# command_radiateur.net
KiCad netlist of a schematic drawn in EAGLE
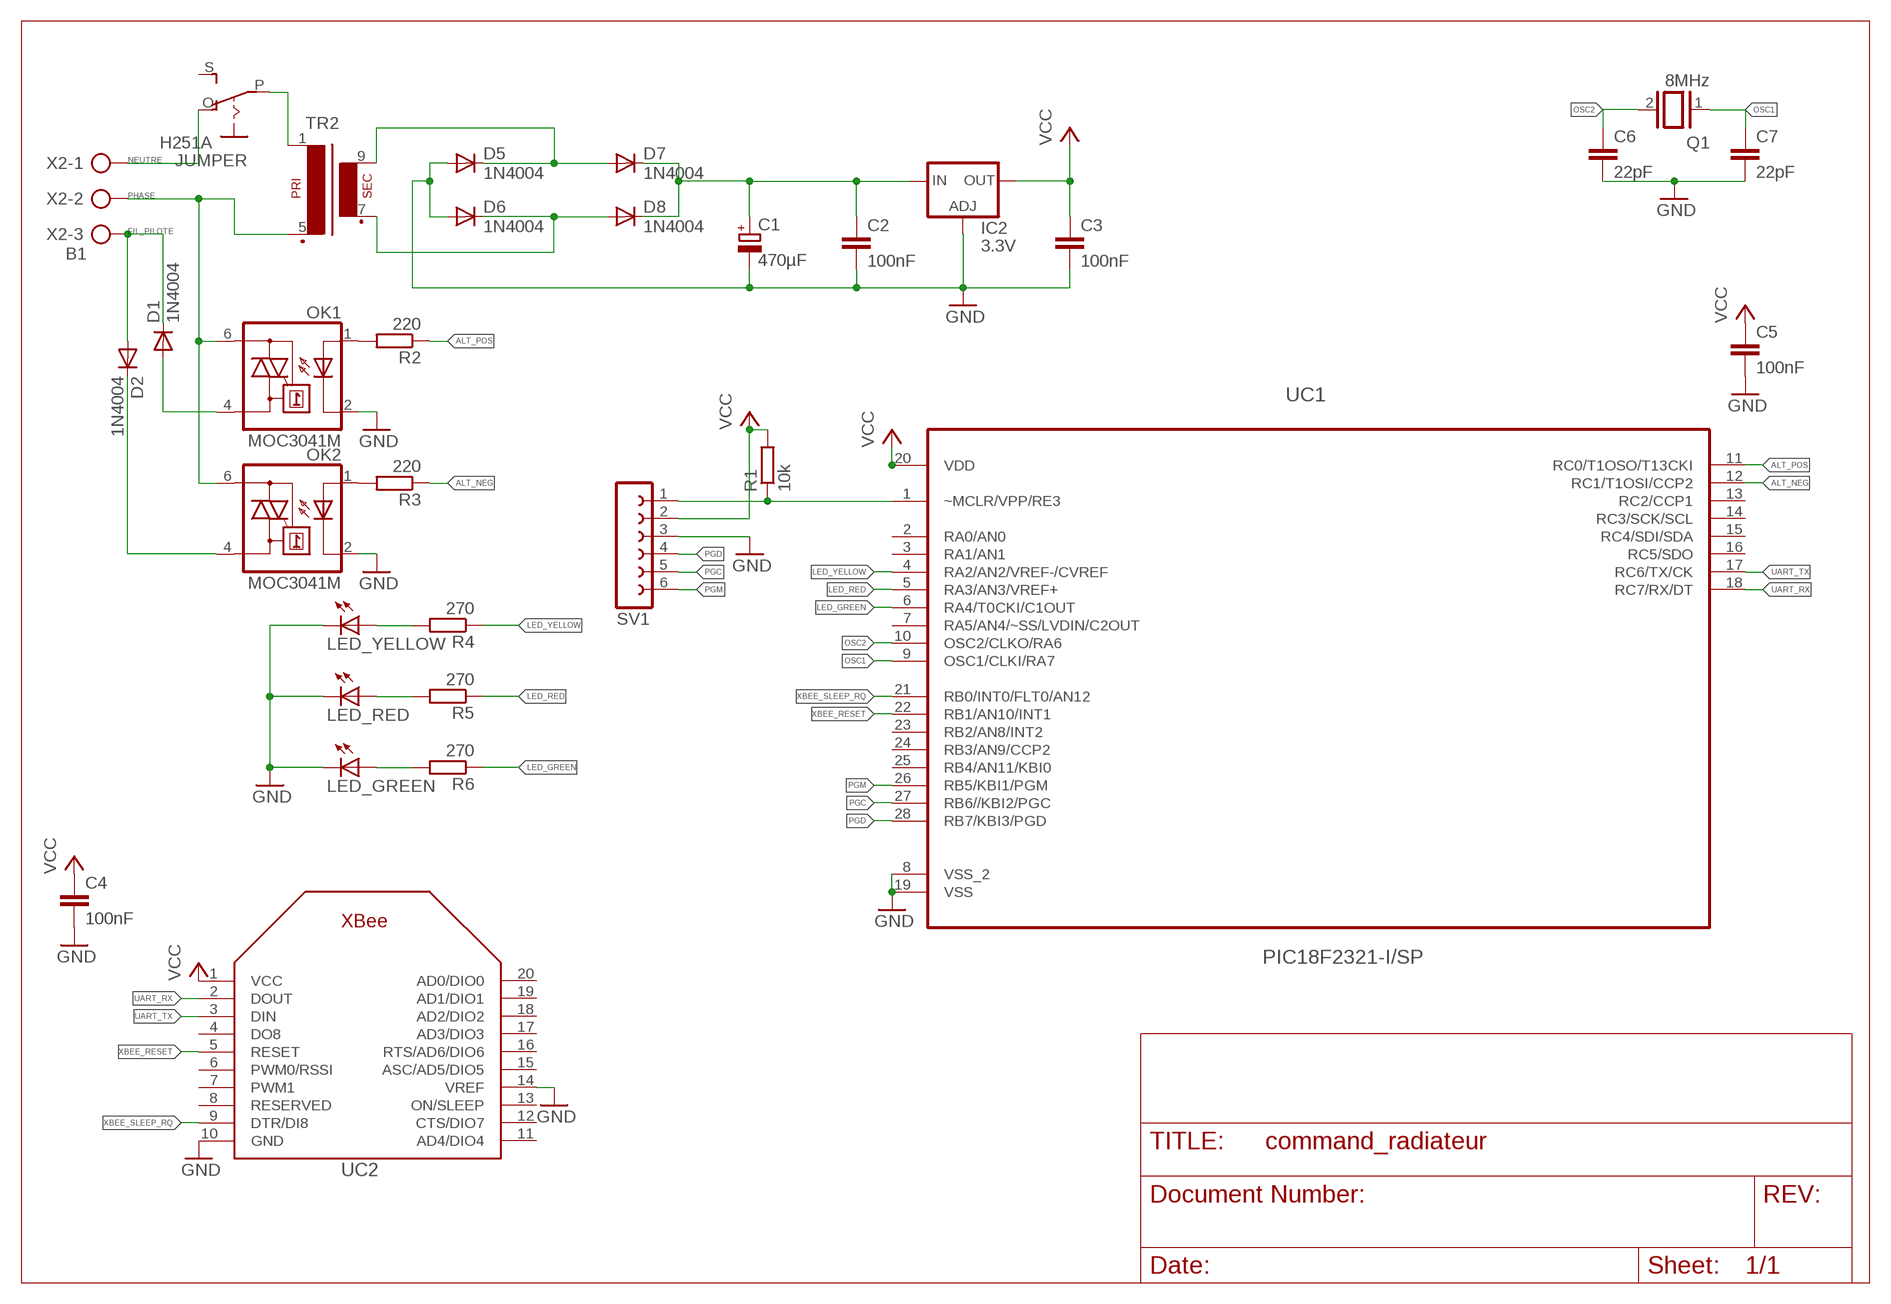
[diagram p0: schematic, sheet 1]

(export (version "E")
  (design (tool "Eeschema 10.0.6"))
  (components
    (comp (ref "C1")
      (value "470µF")
      (footprint "eagle-import:E5-10,5")
      (libsource (lib "eagle-import") (part "CPOL-EUE5-10.5"))
    )
    (comp (ref "C2")
      (value "100nF")
      (footprint "eagle-import:C050-030X075")
      (libsource (lib "eagle-import") (part "C-EU050-030X075"))
    )
    (comp (ref "C3")
      (value "100nF")
      (footprint "eagle-import:C050-030X075")
      (libsource (lib "eagle-import") (part "C-EU050-030X075"))
    )
    (comp (ref "C4")
      (value "100nF")
      (footprint "eagle-import:C050-030X075")
      (libsource (lib "eagle-import") (part "C-EU050-030X075"))
    )
    (comp (ref "C5")
      (value "100nF")
      (footprint "eagle-import:C050-030X075")
      (libsource (lib "eagle-import") (part "C-EU050-030X075"))
    )
    (comp (ref "C6")
      (value "22pF")
      (footprint "eagle-import:C025-024X044")
      (libsource (lib "eagle-import") (part "C-EU025-024X044"))
    )
    (comp (ref "C7")
      (value "22pF")
      (footprint "eagle-import:C025-024X044")
      (libsource (lib "eagle-import") (part "C-EU025-024X044"))
    )
    (comp (ref "D1")
      (value "1N4004")
      (footprint "eagle-import:DO41-10")
      (libsource (lib "eagle-import") (part "1N4004"))
    )
    (comp (ref "D2")
      (value "1N4004")
      (footprint "eagle-import:DO41-10")
      (libsource (lib "eagle-import") (part "1N4004"))
    )
    (comp (ref "D5")
      (value "1N4004")
      (footprint "eagle-import:DO41-10")
      (libsource (lib "eagle-import") (part "1N4004"))
    )
    (comp (ref "D6")
      (value "1N4004")
      (footprint "eagle-import:DO41-10")
      (libsource (lib "eagle-import") (part "1N4004"))
    )
    (comp (ref "D7")
      (value "1N4004")
      (footprint "eagle-import:DO41-10")
      (libsource (lib "eagle-import") (part "1N4004"))
    )
    (comp (ref "D8")
      (value "1N4004")
      (footprint "eagle-import:DO41-10")
      (libsource (lib "eagle-import") (part "1N4004"))
    )
    (comp (ref "IC2")
      (value "3.3V")
      (footprint "eagle-import:317TS")
      (libsource (lib "eagle-import") (part "LM317TS"))
    )
    (comp (ref "JUMPER")
      (value "H251A")
      (footprint "eagle-import:H251A")
      (libsource (lib "eagle-import") (part "H251A"))
    )
    (comp (ref "LED_GREEN")
      (value "LED3MM")
      (footprint "eagle-import:LED3MM")
      (libsource (lib "eagle-import") (part "LED3MM"))
    )
    (comp (ref "LED_RED")
      (value "LED3MM")
      (footprint "eagle-import:LED3MM")
      (libsource (lib "eagle-import") (part "LED3MM"))
    )
    (comp (ref "LED_YELLOW")
      (value "LED3MM")
      (footprint "eagle-import:LED3MM")
      (libsource (lib "eagle-import") (part "LED3MM"))
    )
    (comp (ref "OK1")
      (value "MOC3041M")
      (footprint "eagle-import:DIL06")
      (fields (field (name "MF") "FAIRCHILD SEMICONDUCTOR"))
      (libsource (lib "eagle-import") (part "MOC3041M"))
    )
    (comp (ref "OK2")
      (value "MOC3041M")
      (footprint "eagle-import:DIL06")
      (fields (field (name "MF") "FAIRCHILD SEMICONDUCTOR"))
      (libsource (lib "eagle-import") (part "MOC3041M"))
    )
    (comp (ref "Q1")
      (value "8MHz")
      (footprint "eagle-import:QS")
      (libsource (lib "eagle-import") (part "XTAL/S"))
    )
    (comp (ref "R1")
      (value "10k")
      (footprint "eagle-import:0204_7")
      (libsource (lib "eagle-import") (part "R-EU_0204/7"))
    )
    (comp (ref "R2")
      (value "220")
      (footprint "eagle-import:0204_7")
      (libsource (lib "eagle-import") (part "R-EU_0204/7"))
    )
    (comp (ref "R3")
      (value "220")
      (footprint "eagle-import:0204_7")
      (libsource (lib "eagle-import") (part "R-EU_0204/7"))
    )
    (comp (ref "R4")
      (value "270")
      (footprint "eagle-import:0204_7")
      (libsource (lib "eagle-import") (part "R-EU_0204/7"))
    )
    (comp (ref "R5")
      (value "270")
      (footprint "eagle-import:0204_7")
      (libsource (lib "eagle-import") (part "R-EU_0204/7"))
    )
    (comp (ref "R6")
      (value "270")
      (footprint "eagle-import:0204_7")
      (libsource (lib "eagle-import") (part "R-EU_0204/7"))
    )
    (comp (ref "SV1")
      (value "FE06-1")
      (footprint "eagle-import:FE06")
      (libsource (lib "eagle-import") (part "FE06-1"))
    )
    (comp (ref "TR2")
      (value "VV11")
      (footprint "eagle-import:VV11")
      (libsource (lib "eagle-import") (part "VV11"))
    )
    (comp (ref "UC1")
      (value "PIC18F2321-I/SP")
      (footprint "eagle-import:DIP254P762X508-28")
      (libsource (lib "eagle-import") (part "PIC18F2321-I/SP"))
    )
    (comp (ref "UC2")
      (value "XBEE")
      (footprint "eagle-import:XBEE")
      (libsource (lib "eagle-import") (part "XBEE"))
    )
    (comp (ref "X2")
      (value "B1")
      (footprint "eagle-import:AK300_3")
      (libsource (lib "eagle-import") (part "AK300/3"))
    )
  )
  (nets
    (net (code "1") (name "/FIL_PILOTE") (class "Default")
      (node (ref "D1") (pin "C") (pinfunction "C_C") (pintype "passive"))
      (node (ref "D2") (pin "A") (pinfunction "A_A") (pintype "passive"))
      (node (ref "X2") (pin "3") (pinfunction "KL_3") (pintype "passive"))
    )
    (net (code "2") (name "/NEUTRE") (class "Default")
      (node (ref "JUMPER") (pin "O") (pinfunction "O_O") (pintype "passive"))
      (node (ref "X2") (pin "1") (pinfunction "KL_1") (pintype "passive"))
    )
    (net (code "3") (name "/PHASE") (class "Default")
      (node (ref "OK1") (pin "6") (pinfunction "A2_6") (pintype "passive"))
      (node (ref "OK2") (pin "6") (pinfunction "A2_6") (pintype "passive"))
      (node (ref "TR2") (pin "5") (pinfunction "P2_5") (pintype "passive"))
      (node (ref "X2") (pin "2") (pinfunction "KL_2") (pintype "passive"))
    )
    (net (code "4") (name "ALT_NEG") (class "Default")
      (node (ref "R3") (pin "1") (pinfunction "1_1") (pintype "passive"))
      (node (ref "UC1") (pin "12") (pinfunction "RC1/T1OSI/CCP2_12") (pintype "bidirectional"))
    )
    (net (code "5") (name "ALT_POS") (class "Default")
      (node (ref "R2") (pin "1") (pinfunction "1_1") (pintype "passive"))
      (node (ref "UC1") (pin "11") (pinfunction "RC0/T1OSO/T13CKI_11") (pintype "bidirectional"))
    )
    (net (code "6") (name "GND") (class "Default")
      (node (ref "C1") (pin "-") (pinfunction "-_-") (pintype "passive"))
      (node (ref "C2") (pin "2") (pinfunction "2_2") (pintype "passive"))
      (node (ref "C3") (pin "2") (pinfunction "2_2") (pintype "passive"))
      (node (ref "C4") (pin "2") (pinfunction "2_2") (pintype "passive"))
      (node (ref "C5") (pin "2") (pinfunction "2_2") (pintype "passive"))
      (node (ref "C6") (pin "2") (pinfunction "2_2") (pintype "passive"))
      (node (ref "C7") (pin "2") (pinfunction "2_2") (pintype "passive"))
      (node (ref "D5") (pin "A") (pinfunction "A_A") (pintype "passive"))
      (node (ref "D6") (pin "A") (pinfunction "A_A") (pintype "passive"))
      (node (ref "IC2") (pin "1") (pinfunction "ADJ_1") (pintype "input"))
      (node (ref "LED_GREEN") (pin "K") (pinfunction "C_K") (pintype "passive"))
      (node (ref "LED_RED") (pin "K") (pinfunction "C_K") (pintype "passive"))
      (node (ref "LED_YELLOW") (pin "K") (pinfunction "C_K") (pintype "passive"))
      (node (ref "OK1") (pin "2") (pinfunction "C_2") (pintype "passive"))
      (node (ref "OK2") (pin "2") (pinfunction "C_2") (pintype "passive"))
      (node (ref "SV1") (pin "3") (pinfunction "3_3") (pintype "passive"))
      (node (ref "UC1") (pin "19") (pinfunction "VSS_19") (pintype "passive"))
      (node (ref "UC1") (pin "8") (pinfunction "VSS_2_8") (pintype "passive"))
      (node (ref "UC2") (pin "10") (pinfunction "GND_10") (pintype "power_in"))
      (node (ref "UC2") (pin "14") (pinfunction "VREF_14") (pintype "input"))
    )
    (net (code "7") (name "LED_GREEN") (class "Default")
      (node (ref "R6") (pin "1") (pinfunction "1_1") (pintype "passive"))
      (node (ref "UC1") (pin "6") (pinfunction "RA4/T0CKI/C1OUT_6") (pintype "bidirectional"))
    )
    (net (code "8") (name "LED_RED") (class "Default")
      (node (ref "R5") (pin "1") (pinfunction "1_1") (pintype "passive"))
      (node (ref "UC1") (pin "5") (pinfunction "RA3/AN3/VREF+_5") (pintype "bidirectional"))
    )
    (net (code "9") (name "LED_YELLOW") (class "Default")
      (node (ref "R4") (pin "1") (pinfunction "1_1") (pintype "passive"))
      (node (ref "UC1") (pin "4") (pinfunction "RA2/AN2/VREF-/CVREF_4") (pintype "bidirectional"))
    )
    (net (code "10") (name "Net-(IC2-IN)") (class "Default")
      (node (ref "C1") (pin "+") (pinfunction "+_+") (pintype "passive"))
      (node (ref "C2") (pin "1") (pinfunction "1_1") (pintype "passive"))
      (node (ref "D7") (pin "C") (pinfunction "C_C") (pintype "passive"))
      (node (ref "D8") (pin "C") (pinfunction "C_C") (pintype "passive"))
      (node (ref "IC2") (pin "3") (pinfunction "IN_3") (pintype "input"))
    )
    (net (code "11") (name "Net-(LED_GREEN-PadA)") (class "Default")
      (node (ref "LED_GREEN") (pin "A") (pinfunction "A_A") (pintype "passive"))
      (node (ref "R6") (pin "2") (pinfunction "2_2") (pintype "passive"))
    )
    (net (code "12") (name "Net-(LED_RED-PadA)") (class "Default")
      (node (ref "LED_RED") (pin "A") (pinfunction "A_A") (pintype "passive"))
      (node (ref "R5") (pin "2") (pinfunction "2_2") (pintype "passive"))
    )
    (net (code "13") (name "Net-(LED_YELLOW-PadA)") (class "Default")
      (node (ref "LED_YELLOW") (pin "A") (pinfunction "A_A") (pintype "passive"))
      (node (ref "R4") (pin "2") (pinfunction "2_2") (pintype "passive"))
    )
    (net (code "14") (name "Net-(OK1-A)") (class "Default")
      (node (ref "OK1") (pin "1") (pinfunction "A_1") (pintype "passive"))
      (node (ref "R2") (pin "2") (pinfunction "2_2") (pintype "passive"))
    )
    (net (code "15") (name "Net-(OK1-A1)") (class "Default")
      (node (ref "D1") (pin "A") (pinfunction "A_A") (pintype "passive"))
      (node (ref "OK1") (pin "4") (pinfunction "A1_4") (pintype "passive"))
    )
    (net (code "16") (name "Net-(OK2-A)") (class "Default")
      (node (ref "OK2") (pin "1") (pinfunction "A_1") (pintype "passive"))
      (node (ref "R3") (pin "2") (pinfunction "2_2") (pintype "passive"))
    )
    (net (code "17") (name "Net-(OK2-A1)") (class "Default")
      (node (ref "D2") (pin "C") (pinfunction "C_C") (pintype "passive"))
      (node (ref "OK2") (pin "4") (pinfunction "A1_4") (pintype "passive"))
    )
    (net (code "18") (name "Net-(TR2-P1)") (class "Default")
      (node (ref "JUMPER") (pin "P") (pinfunction "P_P") (pintype "passive"))
      (node (ref "TR2") (pin "1") (pinfunction "P1_1") (pintype "passive"))
    )
    (net (code "19") (name "Net-(TR2-S3)") (class "Default")
      (node (ref "D6") (pin "C") (pinfunction "C_C") (pintype "passive"))
      (node (ref "D8") (pin "A") (pinfunction "A_A") (pintype "passive"))
      (node (ref "TR2") (pin "7") (pinfunction "S3_7") (pintype "passive"))
    )
    (net (code "20") (name "Net-(TR2-S4)") (class "Default")
      (node (ref "D5") (pin "C") (pinfunction "C_C") (pintype "passive"))
      (node (ref "D7") (pin "A") (pinfunction "A_A") (pintype "passive"))
      (node (ref "TR2") (pin "9") (pinfunction "S4_9") (pintype "passive"))
    )
    (net (code "21") (name "Net-(UC1-~{MCLR{slash}VPP{slash}RE3})") (class "Default")
      (node (ref "R1") (pin "1") (pinfunction "1_1") (pintype "passive"))
      (node (ref "SV1") (pin "1") (pinfunction "1_1") (pintype "passive"))
      (node (ref "UC1") (pin "1") (pinfunction "~{MCLR/VPP/RE3}_1") (pintype "input"))
    )
    (net (code "22") (name "OSC1") (class "Default")
      (node (ref "C7") (pin "1") (pinfunction "1_1") (pintype "passive"))
      (node (ref "Q1") (pin "1") (pinfunction "1_1") (pintype "passive"))
      (node (ref "UC1") (pin "9") (pinfunction "OSC1/CLKI/RA7_9") (pintype "bidirectional"))
    )
    (net (code "23") (name "OSC2") (class "Default")
      (node (ref "C6") (pin "1") (pinfunction "1_1") (pintype "passive"))
      (node (ref "Q1") (pin "2") (pinfunction "2_2") (pintype "passive"))
      (node (ref "UC1") (pin "10") (pinfunction "OSC2/CLKO/RA6_10") (pintype "bidirectional"))
    )
    (net (code "24") (name "PGC") (class "Default")
      (node (ref "SV1") (pin "5") (pinfunction "5_5") (pintype "passive"))
      (node (ref "UC1") (pin "27") (pinfunction "RB6//KBI2/PGC_27") (pintype "bidirectional"))
    )
    (net (code "25") (name "PGD") (class "Default")
      (node (ref "SV1") (pin "4") (pinfunction "4_4") (pintype "passive"))
      (node (ref "UC1") (pin "28") (pinfunction "RB7/KBI3/PGD_28") (pintype "bidirectional"))
    )
    (net (code "26") (name "PGM") (class "Default")
      (node (ref "SV1") (pin "6") (pinfunction "6_6") (pintype "passive"))
      (node (ref "UC1") (pin "26") (pinfunction "RB5/KBI1/PGM_26") (pintype "bidirectional"))
    )
    (net (code "27") (name "UART_RX") (class "Default")
      (node (ref "UC1") (pin "18") (pinfunction "RC7/RX/DT_18") (pintype "bidirectional"))
      (node (ref "UC2") (pin "2") (pinfunction "DOUT_2") (pintype "output"))
    )
    (net (code "28") (name "UART_TX") (class "Default")
      (node (ref "UC1") (pin "17") (pinfunction "RC6/TX/CK_17") (pintype "bidirectional"))
      (node (ref "UC2") (pin "3") (pinfunction "DIN_3") (pintype "input"))
    )
    (net (code "29") (name "VCC") (class "Default")
      (node (ref "C3") (pin "1") (pinfunction "1_1") (pintype "passive"))
      (node (ref "C4") (pin "1") (pinfunction "1_1") (pintype "passive"))
      (node (ref "C5") (pin "1") (pinfunction "1_1") (pintype "passive"))
      (node (ref "IC2") (pin "2") (pinfunction "OUT_2") (pintype "passive"))
      (node (ref "R1") (pin "2") (pinfunction "2_2") (pintype "passive"))
      (node (ref "SV1") (pin "2") (pinfunction "2_2") (pintype "passive"))
      (node (ref "UC1") (pin "20") (pinfunction "VDD_20") (pintype "power_in"))
      (node (ref "UC2") (pin "1") (pinfunction "VCC_1") (pintype "power_in"))
    )
    (net (code "30") (name "XBEE_RESET") (class "Default")
      (node (ref "UC1") (pin "22") (pinfunction "RB1/AN10/INT1_22") (pintype "bidirectional"))
      (node (ref "UC2") (pin "5") (pinfunction "RESET_5") (pintype "input"))
    )
    (net (code "31") (name "XBEE_SLEEP_RQ") (class "Default")
      (node (ref "UC1") (pin "21") (pinfunction "RB0/INT0/FLT0/AN12_21") (pintype "bidirectional"))
      (node (ref "UC2") (pin "9") (pinfunction "DTR/DI8_9") (pintype "input"))
    )
    (net (code "32") (name "unconnected-(JUMPER-PadS)") (class "Default")
      (node (ref "JUMPER") (pin "S") (pinfunction "S_S") (pintype "passive"))
    )
    (net (code "33") (name "unconnected-(UC1-RA0{slash}AN0-Pad2)") (class "Default")
      (node (ref "UC1") (pin "2") (pinfunction "RA0/AN0_2") (pintype "bidirectional"))
    )
    (net (code "34") (name "unconnected-(UC1-RA1{slash}AN1-Pad3)") (class "Default")
      (node (ref "UC1") (pin "3") (pinfunction "RA1/AN1_3") (pintype "bidirectional"))
    )
    (net (code "35") (name "unconnected-(UC1-RA5{slash}AN4{slash}~{SS{slash}LVDIN{slash}C2OUT}-Pad7)") (class "Default")
      (node (ref "UC1") (pin "7") (pinfunction "RA5/AN4/~{SS/LVDIN/C2OUT}_7") (pintype "bidirectional"))
    )
    (net (code "36") (name "unconnected-(UC1-RB2{slash}AN8{slash}INT2-Pad23)") (class "Default")
      (node (ref "UC1") (pin "23") (pinfunction "RB2/AN8/INT2_23") (pintype "bidirectional"))
    )
    (net (code "37") (name "unconnected-(UC1-RB3{slash}AN9{slash}CCP2-Pad24)") (class "Default")
      (node (ref "UC1") (pin "24") (pinfunction "RB3/AN9/CCP2_24") (pintype "bidirectional"))
    )
    (net (code "38") (name "unconnected-(UC1-RB4{slash}AN11{slash}KBI0-Pad25)") (class "Default")
      (node (ref "UC1") (pin "25") (pinfunction "RB4/AN11/KBI0_25") (pintype "bidirectional"))
    )
    (net (code "39") (name "unconnected-(UC1-RC2{slash}CCP1-Pad13)") (class "Default")
      (node (ref "UC1") (pin "13") (pinfunction "RC2/CCP1_13") (pintype "bidirectional"))
    )
    (net (code "40") (name "unconnected-(UC1-RC3{slash}SCK{slash}SCL-Pad14)") (class "Default")
      (node (ref "UC1") (pin "14") (pinfunction "RC3/SCK/SCL_14") (pintype "bidirectional"))
    )
    (net (code "41") (name "unconnected-(UC1-RC4{slash}SDI{slash}SDA-Pad15)") (class "Default")
      (node (ref "UC1") (pin "15") (pinfunction "RC4/SDI/SDA_15") (pintype "bidirectional"))
    )
    (net (code "42") (name "unconnected-(UC1-RC5{slash}SDO-Pad16)") (class "Default")
      (node (ref "UC1") (pin "16") (pinfunction "RC5/SDO_16") (pintype "bidirectional"))
    )
    (net (code "43") (name "unconnected-(UC2-AD0{slash}DIO0-Pad20)") (class "Default")
      (node (ref "UC2") (pin "20") (pinfunction "AD0/DIO0_20") (pintype "bidirectional"))
    )
    (net (code "44") (name "unconnected-(UC2-AD1{slash}DIO1-Pad19)") (class "Default")
      (node (ref "UC2") (pin "19") (pinfunction "AD1/DIO1_19") (pintype "bidirectional"))
    )
    (net (code "45") (name "unconnected-(UC2-AD2{slash}DIO2-Pad18)") (class "Default")
      (node (ref "UC2") (pin "18") (pinfunction "AD2/DIO2_18") (pintype "bidirectional"))
    )
    (net (code "46") (name "unconnected-(UC2-AD3{slash}DIO3-Pad17)") (class "Default")
      (node (ref "UC2") (pin "17") (pinfunction "AD3/DIO3_17") (pintype "bidirectional"))
    )
    (net (code "47") (name "unconnected-(UC2-AD4{slash}DIO4-Pad11)") (class "Default")
      (node (ref "UC2") (pin "11") (pinfunction "AD4/DIO4_11") (pintype "bidirectional"))
    )
    (net (code "48") (name "unconnected-(UC2-ASC{slash}AD5{slash}DIO5-Pad15)") (class "Default")
      (node (ref "UC2") (pin "15") (pinfunction "ASC/AD5/DIO5_15") (pintype "bidirectional"))
    )
    (net (code "49") (name "unconnected-(UC2-CTS{slash}DIO7-Pad12)") (class "Default")
      (node (ref "UC2") (pin "12") (pinfunction "CTS/DIO7_12") (pintype "bidirectional"))
    )
    (net (code "50") (name "unconnected-(UC2-DO8-Pad4)") (class "Default")
      (node (ref "UC2") (pin "4") (pinfunction "DO8_4") (pintype "output"))
    )
    (net (code "51") (name "unconnected-(UC2-ON{slash}SLEEP-Pad13)") (class "Default")
      (node (ref "UC2") (pin "13") (pinfunction "ON/SLEEP_13") (pintype "output"))
    )
    (net (code "52") (name "unconnected-(UC2-PWM0{slash}RSSI-Pad6)") (class "Default")
      (node (ref "UC2") (pin "6") (pinfunction "PWM0/RSSI_6") (pintype "output"))
    )
    (net (code "53") (name "unconnected-(UC2-PWM1-Pad7)") (class "Default")
      (node (ref "UC2") (pin "7") (pinfunction "PWM1_7") (pintype "output"))
    )
    (net (code "54") (name "unconnected-(UC2-RESERVED-Pad8)") (class "Default")
      (node (ref "UC2") (pin "8") (pinfunction "RESERVED_8") (pintype "no_connect"))
    )
    (net (code "55") (name "unconnected-(UC2-RTS{slash}AD6{slash}DIO6-Pad16)") (class "Default")
      (node (ref "UC2") (pin "16") (pinfunction "RTS/AD6/DIO6_16") (pintype "bidirectional"))
    )
  )
)
